# TC2050-NL_TagConnect_10-pin.net
KiCad netlist of a schematic drawn in Altium Designer
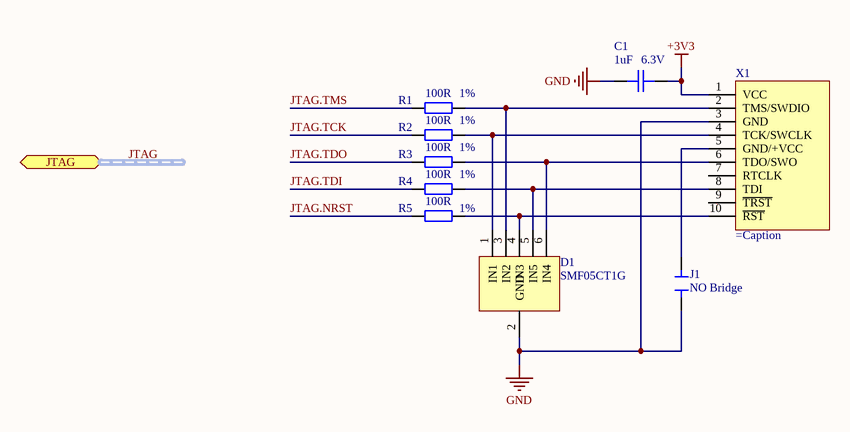
[diagram p0: TC2050-NL_TagConnect_10-pin.SchDoc]

(export (version "E")
  (design (tool "Eeschema 10.0.6"))
  (components
    (comp (ref "C1")
      (value "CAP CER 1UF 6.3V X5R 0402")
      (footprint "C0402")
      (description "1µF ±10% 6.3V Ceramic Capacitor X5R 0402 (1005 Metric)")
      (fields
        (field (name "MANUFACTURER") "Yageo")
        (field (name "MANUFACTURER PART NUMBER") "CC0402KRX5R5BB105")
        (field (name "CAPACITANCE") "1uF")
        (field (name "VOLTAGE RATING") "6.3V")
      )
      (libsource (lib "capacitors_smd") (part "CAP CER 1UF 6.3V X5R 0402"))
    )
    (comp (ref "D1")
      (value "SMF05CT1G")
      (footprint "SOT363_SOP65P210X265-6N")
      (description "12.5V Clamp 8A (8/20µs) Ipp Tvs Diode Surface Mount SC-88/SC70-6/SOT-363")
      (fields (field (name "MANUFACTURER") "ON Semiconductor"))
      (libsource (lib "diodes_tvs") (part "TVS DIODE 5V 12.5V 5CH SC88"))
    )
    (comp (ref "J1")
      (value "NO Bridge")
      (footprint "NO_SolderBridge_0603")
      (description "NO PCB Bridge (May be closed by a solder blob)")
      (libsource (lib "RelibondHMI") (part "NO Bridge"))
    )
    (comp (ref "R1")
      (value "RES SMD 100 OHM 1% 1/16W 0402")
      (footprint "R0402")
      (description "100 Ohms ±1% 0.063W, 1/16W Chip Resistor 0402 (1005 Metric) Moisture Resistant Thick Film")
      (fields
        (field (name "MANUFACTURER") "Yageo")
        (field (name "MANUFACTURER PART NUMBER") "RC0402FR-07100RL")
        (field (name "TOLERANCE") "1%")
        (field (name "RESISTANCE") "100R")
      )
      (libsource (lib "resistors_smd") (part "RES SMD 100 OHM 1% 1/16W 0402"))
    )
    (comp (ref "R2")
      (value "RES SMD 100 OHM 1% 1/16W 0402")
      (footprint "R0402")
      (description "100 Ohms ±1% 0.063W, 1/16W Chip Resistor 0402 (1005 Metric) Moisture Resistant Thick Film")
      (fields
        (field (name "MANUFACTURER") "Yageo")
        (field (name "MANUFACTURER PART NUMBER") "RC0402FR-07100RL")
        (field (name "TOLERANCE") "1%")
        (field (name "RESISTANCE") "100R")
      )
      (libsource (lib "resistors_smd") (part "RES SMD 100 OHM 1% 1/16W 0402"))
    )
    (comp (ref "R3")
      (value "RES SMD 100 OHM 1% 1/16W 0402")
      (footprint "R0402")
      (description "100 Ohms ±1% 0.063W, 1/16W Chip Resistor 0402 (1005 Metric) Moisture Resistant Thick Film")
      (fields
        (field (name "MANUFACTURER") "Yageo")
        (field (name "MANUFACTURER PART NUMBER") "RC0402FR-07100RL")
        (field (name "TOLERANCE") "1%")
        (field (name "RESISTANCE") "100R")
      )
      (libsource (lib "resistors_smd") (part "RES SMD 100 OHM 1% 1/16W 0402"))
    )
    (comp (ref "R4")
      (value "RES SMD 100 OHM 1% 1/16W 0402")
      (footprint "R0402")
      (description "100 Ohms ±1% 0.063W, 1/16W Chip Resistor 0402 (1005 Metric) Moisture Resistant Thick Film")
      (fields
        (field (name "MANUFACTURER") "Yageo")
        (field (name "MANUFACTURER PART NUMBER") "RC0402FR-07100RL")
        (field (name "TOLERANCE") "1%")
        (field (name "RESISTANCE") "100R")
      )
      (libsource (lib "resistors_smd") (part "RES SMD 100 OHM 1% 1/16W 0402"))
    )
    (comp (ref "R5")
      (value "RES SMD 100 OHM 1% 1/16W 0402")
      (footprint "R0402")
      (description "100 Ohms ±1% 0.063W, 1/16W Chip Resistor 0402 (1005 Metric) Moisture Resistant Thick Film")
      (fields
        (field (name "MANUFACTURER") "Yageo")
        (field (name "MANUFACTURER PART NUMBER") "RC0402FR-07100RL")
        (field (name "TOLERANCE") "1%")
        (field (name "RESISTANCE") "100R")
      )
      (libsource (lib "resistors_smd") (part "RES SMD 100 OHM 1% 1/16W 0402"))
    )
    (comp (ref "X1")
      (value "~")
      (footprint "TC2050-IDC-NL")
      (description "A connection to Plug-Of-Nails™ Adapter Cable")
      (libsource (lib "RelibondHMI") (part "TC2050-IDC-NL-JTAG"))
    )
  )
  (nets
    (net (code "2") (name "+3V3") (class "Default")
      (node (ref "C1") (pin "2") (pinfunction "2_2") (pintype "passive"))
      (node (ref "X1") (pin "1") (pinfunction "VCC_1") (pintype "passive"))
    )
    (net (code "3") (name "/JTAG.NRST") (class "Default")
      (node (ref "R5") (pin "2") (pinfunction "2_2") (pintype "passive"))
    )
    (net (code "4") (name "/JTAG.TCK") (class "Default")
      (node (ref "R2") (pin "2") (pinfunction "2_2") (pintype "passive"))
    )
    (net (code "5") (name "/JTAG.TDI") (class "Default")
      (node (ref "R4") (pin "2") (pinfunction "2_2") (pintype "passive"))
    )
    (net (code "6") (name "/JTAG.TDO") (class "Default")
      (node (ref "R3") (pin "2") (pinfunction "2_2") (pintype "passive"))
    )
    (net (code "7") (name "/JTAG.TMS") (class "Default")
      (node (ref "R1") (pin "2") (pinfunction "2_2") (pintype "passive"))
    )
    (net (code "9") (name "GND") (class "Default")
      (node (ref "C1") (pin "1") (pinfunction "1_1") (pintype "passive"))
      (node (ref "D1") (pin "2") (pinfunction "GND_2") (pintype "power_in"))
      (node (ref "J1") (pin "1") (pinfunction "1_1") (pintype "passive"))
      (node (ref "X1") (pin "3") (pinfunction "GND_3") (pintype "passive"))
    )
    (net (code "10") (name "Net-(D1-IN1)") (class "Default")
      (node (ref "D1") (pin "1") (pinfunction "IN1_1") (pintype "passive"))
      (node (ref "R2") (pin "1") (pinfunction "1_1") (pintype "passive"))
      (node (ref "X1") (pin "4") (pinfunction "TCK/SWCLK_4") (pintype "passive"))
    )
    (net (code "11") (name "Net-(D1-IN2)") (class "Default")
      (node (ref "D1") (pin "3") (pinfunction "IN2_3") (pintype "passive"))
      (node (ref "R1") (pin "1") (pinfunction "1_1") (pintype "passive"))
      (node (ref "X1") (pin "2") (pinfunction "TMS/SWDIO_2") (pintype "passive"))
    )
    (net (code "12") (name "Net-(D1-IN3)") (class "Default")
      (node (ref "D1") (pin "4") (pinfunction "IN3_4") (pintype "passive"))
      (node (ref "R5") (pin "1") (pinfunction "1_1") (pintype "passive"))
      (node (ref "X1") (pin "10") (pinfunction "RST_10") (pintype "passive"))
    )
    (net (code "13") (name "Net-(D1-IN4)") (class "Default")
      (node (ref "D1") (pin "6") (pinfunction "IN4_6") (pintype "passive"))
      (node (ref "R3") (pin "1") (pinfunction "1_1") (pintype "passive"))
      (node (ref "X1") (pin "6") (pinfunction "TDO/SWO_6") (pintype "passive"))
    )
    (net (code "14") (name "Net-(D1-IN5)") (class "Default")
      (node (ref "D1") (pin "5") (pinfunction "IN5_5") (pintype "passive"))
      (node (ref "R4") (pin "1") (pinfunction "1_1") (pintype "passive"))
      (node (ref "X1") (pin "8") (pinfunction "TDI_8") (pintype "passive"))
    )
    (net (code "15") (name "Net-(X1-GND{slash}+VCC)") (class "Default")
      (node (ref "J1") (pin "2") (pinfunction "2_2") (pintype "passive"))
      (node (ref "X1") (pin "5") (pinfunction "GND/+VCC_5") (pintype "passive"))
    )
    (net (code "16") (name "unconnected-(X1-RTCLK-Pad7)") (class "Default")
      (node (ref "X1") (pin "7") (pinfunction "RTCLK_7") (pintype "passive"))
    )
    (net (code "17") (name "unconnected-(X1-TRST-Pad9)") (class "Default")
      (node (ref "X1") (pin "9") (pinfunction "TRST_9") (pintype "passive"))
    )
  )
)
